# analog_frontend.net
KiCad netlist of a schematic drawn in Altium Designer
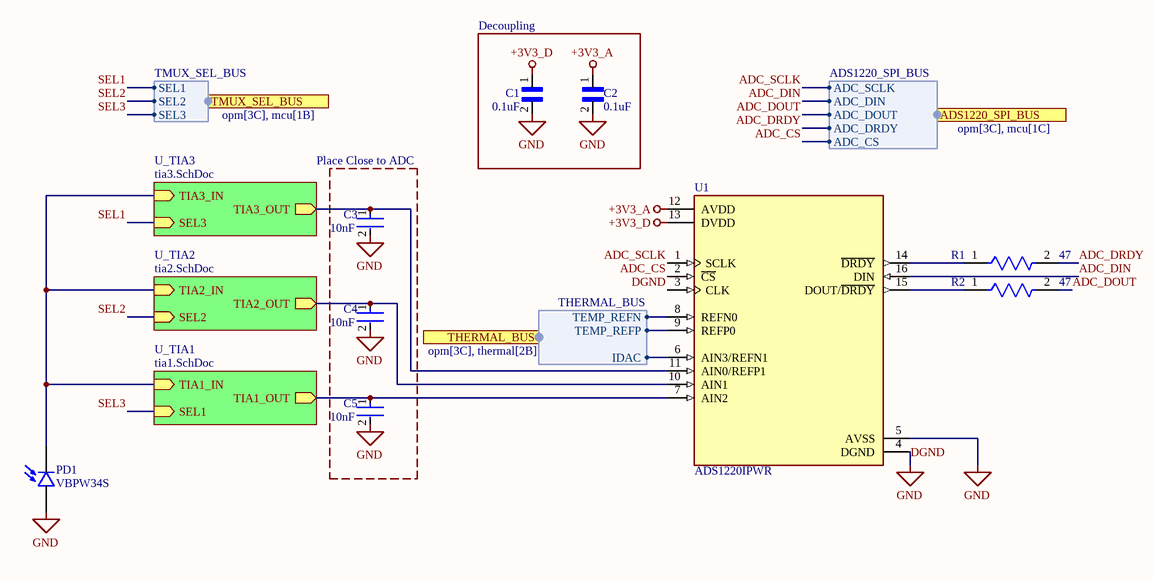
[diagram p0: analog_frontend.SchDoc]

(export (version "E")
  (design (tool "Eeschema 10.0.6"))
  (components
    (comp (ref "C1")
      (value "0.1uF")
      (footprint "CC0603JRX7R8BB104")
      (description "25V 100nF X7R ±5% 0603 Multilayer Ceramic Capacitors MLCC - SMD/SMT ROHS")
      (fields
        (field (name "MANUFACTURER") "Yageo Group")
        (field (name "MANUFACTURER PART NUMBER") "CC0603JRX7R8BB104")
      )
      (libsource (lib "opm_lib") (part "CC0603JRX7R8BB104"))
    )
    (comp (ref "C2")
      (value "0.1uF")
      (footprint "CC0603JRX7R8BB104")
      (description "25V 100nF X7R ±5% 0603 Multilayer Ceramic Capacitors MLCC - SMD/SMT ROHS")
      (fields
        (field (name "MANUFACTURER") "Yageo Group")
        (field (name "MANUFACTURER PART NUMBER") "CC0603JRX7R8BB104")
      )
      (libsource (lib "opm_lib") (part "CC0603JRX7R8BB104"))
    )
    (comp (ref "C3")
      (value "10nF")
      (footprint "GRM1885C1H103JA01D")
      (description "Multilayer Ceramic Capacitor, Grm Series, 0.01 F, 5%, C0g / Np0, 50 V, 0603 [1608 Metric]")
      (fields
        (field (name "MANUFACTURER") "Murata")
        (field (name "MANUFACTURER PART NUMBER") "GRM1885C1H103JA01D")
      )
      (libsource (lib "opm_lib") (part "GRM1885C1H103JA01D"))
    )
    (comp (ref "C4")
      (value "10nF")
      (footprint "GRM1885C1H103JA01D")
      (description "Multilayer Ceramic Capacitor, Grm Series, 0.01 F, 5%, C0g / Np0, 50 V, 0603 [1608 Metric]")
      (fields
        (field (name "MANUFACTURER") "Murata")
        (field (name "MANUFACTURER PART NUMBER") "GRM1885C1H103JA01D")
      )
      (libsource (lib "opm_lib") (part "GRM1885C1H103JA01D"))
    )
    (comp (ref "C5")
      (value "10nF")
      (footprint "GRM1885C1H103JA01D")
      (description "Multilayer Ceramic Capacitor, Grm Series, 0.01 F, 5%, C0g / Np0, 50 V, 0603 [1608 Metric]")
      (fields
        (field (name "MANUFACTURER") "Murata")
        (field (name "MANUFACTURER PART NUMBER") "GRM1885C1H103JA01D")
      )
      (libsource (lib "opm_lib") (part "GRM1885C1H103JA01D"))
    )
    (comp (ref "PD1")
      (value "VBPW34S")
      (footprint "XDCR_VBPW34S")
      (description "IR-photodiode Photoelectric current: 45...55 uA Wavelength of max. photosensitivity: 940 nm")
      (fields (field (name "MANUFACTURER") "Vishay"))
      (libsource (lib "opm_lib") (part "VBPW34S"))
    )
    (comp (ref "R1")
      (value "47")
      (footprint "RC0603FR-07")
      (description "100mW Thick Film Resistors 75V ±100ppm/℃ ±1% 47Ω 0603 Chip Resistor - Surface Mount ROHS")
      (fields
        (field (name "MANUFACTURER") "Yageo Group")
        (field (name "MANUFACTURER PART NUMBER") "RC0603FR-0747RL")
      )
      (libsource (lib "opm_lib") (part "RC0603FR-0747RL"))
    )
    (comp (ref "R2")
      (value "47")
      (footprint "RC0603FR-07")
      (description "100mW Thick Film Resistors 75V ±100ppm/℃ ±1% 47Ω 0603 Chip Resistor - Surface Mount ROHS")
      (fields
        (field (name "MANUFACTURER") "Yageo Group")
        (field (name "MANUFACTURER PART NUMBER") "RC0603FR-0747RL")
      )
      (libsource (lib "opm_lib") (part "RC0603FR-0747RL"))
    )
    (comp (ref "U1")
      (value "ADS1220IPWR")
      (footprint "ADS1220IPWR")
      (description "Single ADC Delta-Sigma 2ksps 24-bit Serial (5-Wire, 4-Wire, 3-Wire, SPI) 16-Pin TSSOP T/R")
      (fields (field (name "MANUFACTURER") "Texas Instruments"))
      (libsource (lib "opm_lib") (part "ADS1220IPWR"))
    )
  )
  (nets
    (net (code "4") (name "+3V3_A") (class "Default")
      (node (ref "C2") (pin "1") (pinfunction "1_1") (pintype "passive"))
      (node (ref "U1") (pin "12") (pinfunction "AVDD_12") (pintype "power_in"))
    )
    (net (code "5") (name "+3V3_D") (class "Default")
      (node (ref "C1") (pin "1") (pinfunction "1_1") (pintype "passive"))
      (node (ref "U1") (pin "13") (pinfunction "DVDD_13") (pintype "power_in"))
    )
    (net (code "6") (name "/ADC_CS") (class "Default")
      (node (ref "U1") (pin "2") (pinfunction "~{CS}_2") (pintype "input"))
    )
    (net (code "7") (name "/ADC_DIN") (class "Default")
      (node (ref "U1") (pin "16") (pinfunction "DIN_16") (pintype "input"))
    )
    (net (code "8") (name "/ADC_DOUT") (class "Default")
      (node (ref "R2") (pin "2") (pinfunction "2_2") (pintype "passive"))
    )
    (net (code "9") (name "/ADC_DRDY") (class "Default")
      (node (ref "R1") (pin "2") (pinfunction "2_2") (pintype "passive"))
    )
    (net (code "10") (name "/ADC_SCLK") (class "Default")
      (node (ref "U1") (pin "1") (pinfunction "SCLK_1") (pintype "input"))
    )
    (net (code "11") (name "/IDAC") (class "Default")
      (node (ref "U1") (pin "6") (pinfunction "AIN3/REFN1_6") (pintype "input"))
    )
    (net (code "15") (name "/TEMP_REFN") (class "Default")
      (node (ref "U1") (pin "8") (pinfunction "REFN0_8") (pintype "input"))
    )
    (net (code "16") (name "/TEMP_REFP") (class "Default")
      (node (ref "U1") (pin "9") (pinfunction "REFP0_9") (pintype "input"))
    )
    (net (code "17") (name "/TIA1_IN") (class "Default")
      (node (ref "PD1") (pin "K") (pinfunction "C_K") (pintype "passive"))
    )
    (net (code "18") (name "/TIA1_OUT") (class "Default")
      (node (ref "C5") (pin "1") (pinfunction "1_1") (pintype "passive"))
      (node (ref "U1") (pin "7") (pinfunction "AIN2_7") (pintype "input"))
    )
    (net (code "19") (name "/TIA2_OUT") (class "Default")
      (node (ref "C4") (pin "1") (pinfunction "1_1") (pintype "passive"))
      (node (ref "U1") (pin "10") (pinfunction "AIN1_10") (pintype "input"))
    )
    (net (code "20") (name "/TIA3_OUT") (class "Default")
      (node (ref "C3") (pin "1") (pinfunction "1_1") (pintype "passive"))
      (node (ref "U1") (pin "11") (pinfunction "AIN0/REFP1_11") (pintype "input"))
    )
    (net (code "24") (name "GND") (class "Default")
      (node (ref "C1") (pin "2") (pinfunction "2_2") (pintype "passive"))
      (node (ref "C2") (pin "2") (pinfunction "2_2") (pintype "passive"))
      (node (ref "C3") (pin "2") (pinfunction "2_2") (pintype "passive"))
      (node (ref "C4") (pin "2") (pinfunction "2_2") (pintype "passive"))
      (node (ref "C5") (pin "2") (pinfunction "2_2") (pintype "passive"))
      (node (ref "PD1") (pin "A") (pinfunction "A_A") (pintype "passive"))
      (node (ref "U1") (pin "3") (pinfunction "CLK_3") (pintype "input"))
      (node (ref "U1") (pin "4") (pinfunction "DGND_4") (pintype "power_in"))
      (node (ref "U1") (pin "5") (pinfunction "AVSS_5") (pintype "power_in"))
    )
    (net (code "25") (name "Net-(U1-DOUT{slash}~{DRDY})") (class "Default")
      (node (ref "R2") (pin "1") (pinfunction "1_1") (pintype "passive"))
      (node (ref "U1") (pin "15") (pinfunction "DOUT/~{DRDY}_15") (pintype "output"))
    )
    (net (code "26") (name "Net-(U1-~{DRDY})") (class "Default")
      (node (ref "R1") (pin "1") (pinfunction "1_1") (pintype "passive"))
      (node (ref "U1") (pin "14") (pinfunction "~{DRDY}_14") (pintype "output"))
    )
  )
)
